# USB2UART.net
KiCad netlist of a schematic drawn in Altium Designer
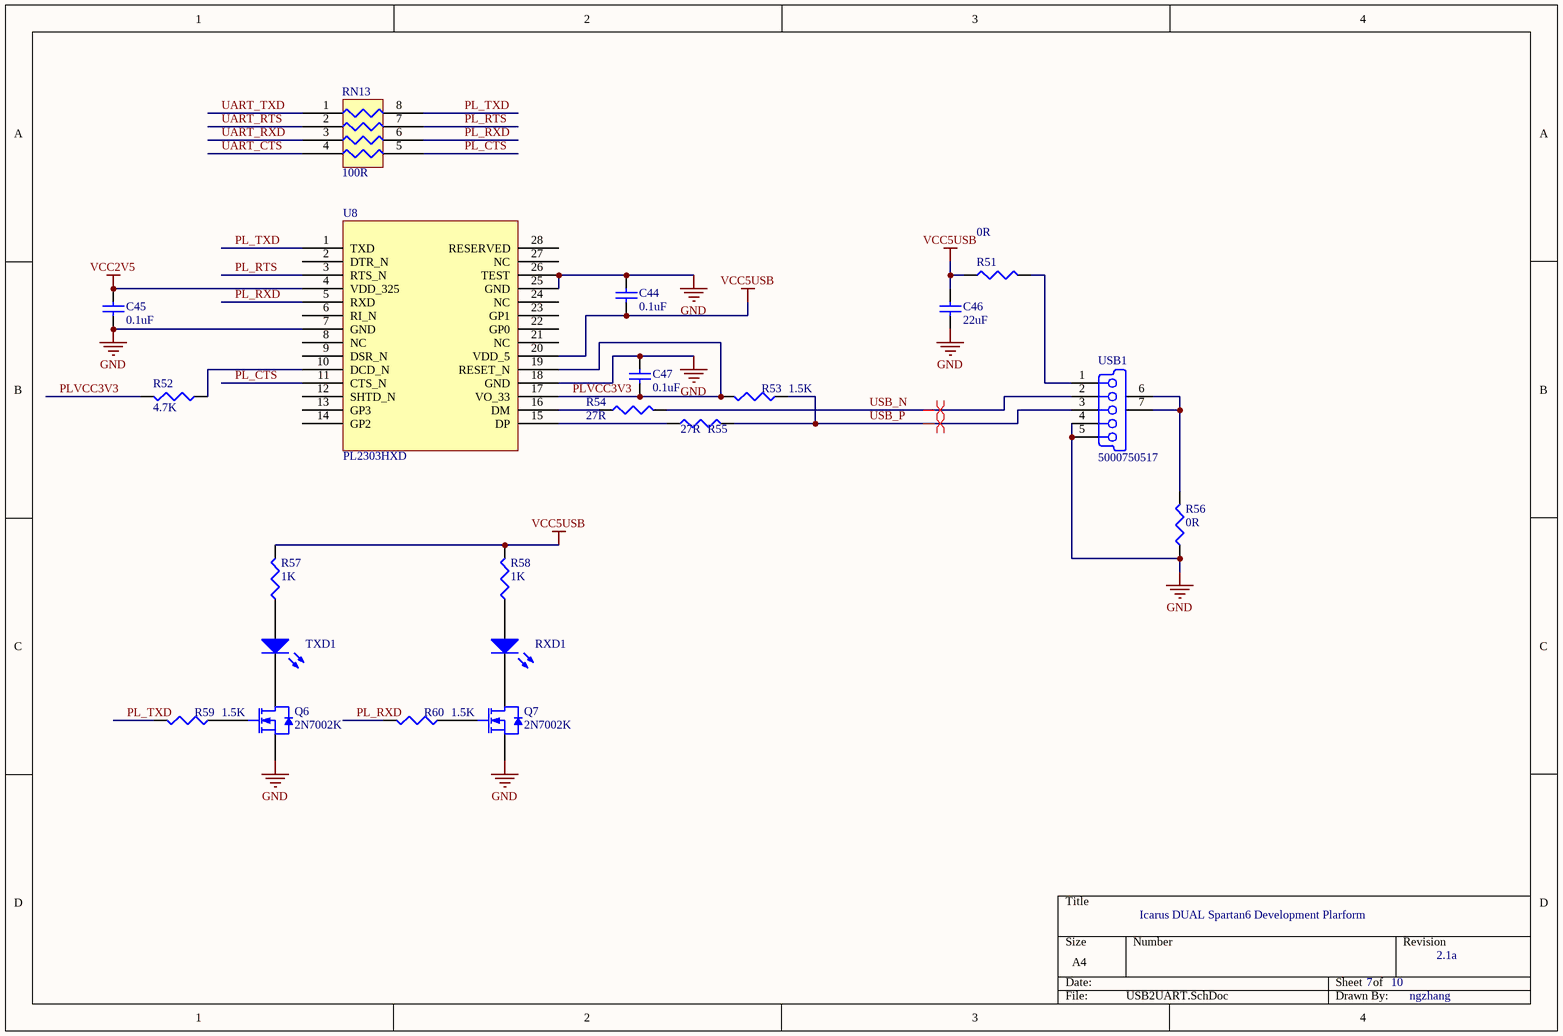
[diagram p0: USB2UART.SchDoc]

(export (version "E")
  (design (tool "Eeschema 10.0.6"))
  (components
    (comp (ref "C44")
      (value "0.1uF")
      (footprint "1608[0603]")
      (description "Capacitor (Semiconductor SIM Model)")
      (fields (field (name "PUBLISHER") "Altium Limited"))
      (libsource (lib "Miscellaneous Devices") (part "Cap Semi"))
    )
    (comp (ref "C45")
      (value "0.1uF")
      (footprint "1608[0603]")
      (description "Capacitor (Semiconductor SIM Model)")
      (fields (field (name "PUBLISHER") "Altium Limited"))
      (libsource (lib "Miscellaneous Devices") (part "Cap Semi"))
    )
    (comp (ref "C46")
      (value "22uF")
      (footprint "C1206")
      (description "Capacitor (Semiconductor SIM Model)")
      (fields (field (name "PUBLISHER") "Altium Limited"))
      (libsource (lib "Miscellaneous Devices") (part "Cap Semi"))
    )
    (comp (ref "C47")
      (value "0.1uF")
      (footprint "1608[0603]")
      (description "Capacitor (Semiconductor SIM Model)")
      (fields (field (name "PUBLISHER") "Altium Limited"))
      (libsource (lib "Miscellaneous Devices") (part "Cap Semi"))
    )
    (comp (ref "Q6")
      (value "2N7002K")
      (footprint "SOT23_N")
      (description "N-channel Enhancement Mode Field-effect Transistor")
      (fields (field (name "PUBLISHER") "Altium Limited"))
      (libsource (lib "Philips Discrete MOSFET - Low Power") (part "2N7002"))
    )
    (comp (ref "Q7")
      (value "2N7002K")
      (footprint "SOT23_N")
      (description "N-channel Enhancement Mode Field-effect Transistor")
      (fields (field (name "PUBLISHER") "Altium Limited"))
      (libsource (lib "Philips Discrete MOSFET - Low Power") (part "2N7002"))
    )
    (comp (ref "R51")
      (value "0R")
      (footprint "J1-0603")
      (description "Resistor")
      (fields (field (name "PUBLISHER") "Altium Limited"))
      (libsource (lib "Miscellaneous Devices") (part "Res3"))
    )
    (comp (ref "R52")
      (value "4.7K")
      (footprint "J1-0603")
      (description "Resistor")
      (fields (field (name "PUBLISHER") "Altium Limited"))
      (libsource (lib "Miscellaneous Devices") (part "Res3"))
    )
    (comp (ref "R53")
      (value "1.5K")
      (footprint "J1-0603")
      (description "Resistor")
      (fields (field (name "PUBLISHER") "Altium Limited"))
      (libsource (lib "Miscellaneous Devices") (part "Res3"))
    )
    (comp (ref "R54")
      (value "27R")
      (footprint "J1-0603")
      (description "Resistor")
      (fields (field (name "PUBLISHER") "Altium Limited"))
      (libsource (lib "Miscellaneous Devices") (part "Res3"))
    )
    (comp (ref "R55")
      (value "27R")
      (footprint "J1-0603")
      (description "Resistor")
      (fields (field (name "PUBLISHER") "Altium Limited"))
      (libsource (lib "Miscellaneous Devices") (part "Res3"))
    )
    (comp (ref "R56")
      (value "0R")
      (footprint "J1-0603")
      (description "Resistor")
      (fields (field (name "PUBLISHER") "Altium Limited"))
      (libsource (lib "Miscellaneous Devices") (part "Res3"))
    )
    (comp (ref "R57")
      (value "1K")
      (footprint "J1-0603")
      (description "Resistor")
      (fields (field (name "PUBLISHER") "Altium Limited"))
      (libsource (lib "Miscellaneous Devices") (part "Res3"))
    )
    (comp (ref "R58")
      (value "1K")
      (footprint "J1-0603")
      (description "Resistor")
      (fields (field (name "PUBLISHER") "Altium Limited"))
      (libsource (lib "Miscellaneous Devices") (part "Res3"))
    )
    (comp (ref "R59")
      (value "1.5K")
      (footprint "J1-0603")
      (description "Resistor")
      (fields (field (name "PUBLISHER") "Altium Limited"))
      (libsource (lib "Miscellaneous Devices") (part "Res3"))
    )
    (comp (ref "R60")
      (value "1.5K")
      (footprint "J1-0603")
      (description "Resistor")
      (fields (field (name "PUBLISHER") "Altium Limited"))
      (libsource (lib "Miscellaneous Devices") (part "Res3"))
    )
    (comp (ref "RN13") (value "100R") (footprint "EXBV8V") (libsource (lib "S6") (part "RES4PACK")))
    (comp (ref "RXD1")
      (value "LED3")
      (footprint "CD1608-0603")
      (description "Typical BLUE SiC LED")
      (fields (field (name "PUBLISHER") "Altium Limited"))
      (libsource (lib "Miscellaneous Devices") (part "LED3"))
    )
    (comp (ref "TXD1")
      (value "LED3")
      (footprint "CD1608-0603")
      (description "Typical BLUE SiC LED")
      (fields (field (name "PUBLISHER") "Altium Limited"))
      (libsource (lib "Miscellaneous Devices") (part "LED3"))
    )
    (comp (ref "U8") (value "PL2303HXD") (footprint "SSOP28_N") (libsource (lib "S6") (part "PL2303")))
    (comp (ref "USB1")
      (value "5000750517")
      (footprint "5000750517")
      (fields (field (name "PUBLISHER") "Altium Limited"))
      (libsource (lib "Molex Serial Bus Mini USB") (part "5000750517"))
    )
  )
  (nets
    (net (code "1") (name "/PLVCC3V3") (class "Default")
      (node (ref "C47") (pin "1") (pinfunction "1_1") (pintype "passive"))
      (node (ref "R52") (pin "2") (pinfunction "2_2") (pintype "passive"))
      (node (ref "R53") (pin "2") (pinfunction "2_2") (pintype "passive"))
      (node (ref "U8") (pin "17") (pinfunction "VO_33_17") (pintype "power_in"))
      (node (ref "U8") (pin "19") (pinfunction "RESET_N_19") (pintype "power_in"))
    )
    (net (code "2") (name "/PL_CTS") (class "Default")
      (node (ref "RN13") (pin "5") (pinfunction "5_5") (pintype "power_in"))
      (node (ref "U8") (pin "11") (pinfunction "CTS_N_11") (pintype "power_in"))
    )
    (net (code "3") (name "/PL_RTS") (class "Default")
      (node (ref "RN13") (pin "7") (pinfunction "7_7") (pintype "power_in"))
      (node (ref "U8") (pin "3") (pinfunction "RTS_N_3") (pintype "power_in"))
    )
    (net (code "4") (name "/PL_RXD") (class "Default")
      (node (ref "R60") (pin "2") (pinfunction "2_2") (pintype "passive"))
      (node (ref "RN13") (pin "6") (pinfunction "6_6") (pintype "power_in"))
      (node (ref "U8") (pin "5") (pinfunction "RXD_5") (pintype "power_in"))
    )
    (net (code "5") (name "/PL_TXD") (class "Default")
      (node (ref "R59") (pin "2") (pinfunction "2_2") (pintype "passive"))
      (node (ref "RN13") (pin "8") (pinfunction "8_8") (pintype "power_in"))
      (node (ref "U8") (pin "1") (pinfunction "TXD_1") (pintype "power_in"))
    )
    (net (code "6") (name "/UART_CTS") (class "Default")
      (node (ref "RN13") (pin "4") (pinfunction "4_4") (pintype "power_in"))
    )
    (net (code "7") (name "/UART_RTS") (class "Default")
      (node (ref "RN13") (pin "2") (pinfunction "2_2") (pintype "power_in"))
    )
    (net (code "8") (name "/UART_RXD") (class "Default")
      (node (ref "RN13") (pin "3") (pinfunction "3_3") (pintype "power_in"))
    )
    (net (code "9") (name "/UART_TXD") (class "Default")
      (node (ref "RN13") (pin "1") (pinfunction "1_1") (pintype "power_in"))
    )
    (net (code "10") (name "/USB_N") (class "Default")
      (node (ref "R54") (pin "2") (pinfunction "2_2") (pintype "passive"))
      (node (ref "USB1") (pin "2") (pinfunction "D-_2") (pintype "passive"))
    )
    (net (code "11") (name "/USB_P") (class "Default")
      (node (ref "R53") (pin "1") (pinfunction "1_1") (pintype "passive"))
      (node (ref "R55") (pin "2") (pinfunction "2_2") (pintype "passive"))
      (node (ref "USB1") (pin "3") (pinfunction "D+_3") (pintype "passive"))
    )
    (net (code "12") (name "GND") (class "Default")
      (node (ref "C44") (pin "2") (pinfunction "2_2") (pintype "passive"))
      (node (ref "C45") (pin "1") (pinfunction "1_1") (pintype "passive"))
      (node (ref "C46") (pin "1") (pinfunction "1_1") (pintype "passive"))
      (node (ref "C47") (pin "2") (pinfunction "2_2") (pintype "passive"))
      (node (ref "Q6") (pin "2") (pinfunction "S_2") (pintype "passive"))
      (node (ref "Q7") (pin "2") (pinfunction "S_2") (pintype "passive"))
      (node (ref "R56") (pin "1") (pinfunction "1_1") (pintype "passive"))
      (node (ref "U8") (pin "18") (pinfunction "GND_18") (pintype "power_in"))
      (node (ref "U8") (pin "25") (pinfunction "GND_25") (pintype "power_in"))
      (node (ref "U8") (pin "26") (pinfunction "TEST_26") (pintype "power_in"))
      (node (ref "U8") (pin "7") (pinfunction "GND_7") (pintype "power_in"))
      (node (ref "USB1") (pin "4") (pinfunction "ID_4") (pintype "passive"))
      (node (ref "USB1") (pin "5") (pinfunction "GND_5") (pintype "passive"))
    )
    (net (code "13") (name "Net-(Q6-D)") (class "Default")
      (node (ref "Q6") (pin "3") (pinfunction "D_3") (pintype "passive"))
      (node (ref "TXD1") (pin "2") (pinfunction "K_2") (pintype "passive"))
    )
    (net (code "14") (name "Net-(Q6-G)") (class "Default")
      (node (ref "Q6") (pin "1") (pinfunction "G_1") (pintype "passive"))
      (node (ref "R59") (pin "1") (pinfunction "1_1") (pintype "passive"))
    )
    (net (code "15") (name "Net-(Q7-D)") (class "Default")
      (node (ref "Q7") (pin "3") (pinfunction "D_3") (pintype "passive"))
      (node (ref "RXD1") (pin "2") (pinfunction "K_2") (pintype "passive"))
    )
    (net (code "16") (name "Net-(Q7-G)") (class "Default")
      (node (ref "Q7") (pin "1") (pinfunction "G_1") (pintype "passive"))
      (node (ref "R60") (pin "1") (pinfunction "1_1") (pintype "passive"))
    )
    (net (code "17") (name "Net-(RXD1-A)") (class "Default")
      (node (ref "R58") (pin "1") (pinfunction "1_1") (pintype "passive"))
      (node (ref "RXD1") (pin "1") (pinfunction "A_1") (pintype "passive"))
    )
    (net (code "18") (name "Net-(TXD1-A)") (class "Default")
      (node (ref "R57") (pin "1") (pinfunction "1_1") (pintype "passive"))
      (node (ref "TXD1") (pin "1") (pinfunction "A_1") (pintype "passive"))
    )
    (net (code "19") (name "Net-(U8-DCD_N)") (class "Default")
      (node (ref "R52") (pin "1") (pinfunction "1_1") (pintype "passive"))
      (node (ref "U8") (pin "10") (pinfunction "DCD_N_10") (pintype "power_in"))
    )
    (net (code "20") (name "Net-(U8-DM)") (class "Default")
      (node (ref "R54") (pin "1") (pinfunction "1_1") (pintype "passive"))
      (node (ref "U8") (pin "16") (pinfunction "DM_16") (pintype "power_in"))
    )
    (net (code "21") (name "Net-(U8-DP)") (class "Default")
      (node (ref "R55") (pin "1") (pinfunction "1_1") (pintype "passive"))
      (node (ref "U8") (pin "15") (pinfunction "DP_15") (pintype "power_in"))
    )
    (net (code "22") (name "Net-(USB1-MH1)") (class "Default")
      (node (ref "R56") (pin "2") (pinfunction "2_2") (pintype "passive"))
      (node (ref "USB1") (pin "6") (pinfunction "MH1_6") (pintype "passive"))
      (node (ref "USB1") (pin "7") (pinfunction "MH2_7") (pintype "passive"))
    )
    (net (code "23") (name "Net-(USB1-V_BUS)") (class "Default")
      (node (ref "R51") (pin "2") (pinfunction "2_2") (pintype "passive"))
      (node (ref "USB1") (pin "1") (pinfunction "V_BUS_1") (pintype "passive"))
    )
    (net (code "24") (name "VCC2V5") (class "Default")
      (node (ref "C45") (pin "2") (pinfunction "2_2") (pintype "passive"))
      (node (ref "U8") (pin "4") (pinfunction "VDD_325_4") (pintype "power_in"))
    )
    (net (code "25") (name "VCC5USB") (class "Default")
      (node (ref "C44") (pin "1") (pinfunction "1_1") (pintype "passive"))
      (node (ref "C46") (pin "2") (pinfunction "2_2") (pintype "passive"))
      (node (ref "R51") (pin "1") (pinfunction "1_1") (pintype "passive"))
      (node (ref "R57") (pin "2") (pinfunction "2_2") (pintype "passive"))
      (node (ref "R58") (pin "2") (pinfunction "2_2") (pintype "passive"))
      (node (ref "U8") (pin "20") (pinfunction "VDD_5_20") (pintype "power_in"))
    )
    (net (code "26") (name "unconnected-(U8-DSR_N-Pad9)") (class "Default")
      (node (ref "U8") (pin "9") (pinfunction "DSR_N_9") (pintype "power_in"))
    )
    (net (code "27") (name "unconnected-(U8-DTR_N-Pad2)") (class "Default")
      (node (ref "U8") (pin "2") (pinfunction "DTR_N_2") (pintype "power_in"))
    )
    (net (code "28") (name "unconnected-(U8-GP0-Pad22)") (class "Default")
      (node (ref "U8") (pin "22") (pinfunction "GP0_22") (pintype "power_in"))
    )
    (net (code "29") (name "unconnected-(U8-GP1-Pad23)") (class "Default")
      (node (ref "U8") (pin "23") (pinfunction "GP1_23") (pintype "power_in"))
    )
    (net (code "30") (name "unconnected-(U8-GP2-Pad14)") (class "Default")
      (node (ref "U8") (pin "14") (pinfunction "GP2_14") (pintype "power_in"))
    )
    (net (code "31") (name "unconnected-(U8-GP3-Pad13)") (class "Default")
      (node (ref "U8") (pin "13") (pinfunction "GP3_13") (pintype "power_in"))
    )
    (net (code "32") (name "unconnected-(U8-NC-Pad8)") (class "Default")
      (node (ref "U8") (pin "8") (pinfunction "NC_8") (pintype "power_in"))
    )
    (net (code "33") (name "unconnected-(U8-NC-Pad21)") (class "Default")
      (node (ref "U8") (pin "21") (pinfunction "NC_21") (pintype "power_in"))
    )
    (net (code "34") (name "unconnected-(U8-NC-Pad24)") (class "Default")
      (node (ref "U8") (pin "24") (pinfunction "NC_24") (pintype "power_in"))
    )
    (net (code "35") (name "unconnected-(U8-NC-Pad27)") (class "Default")
      (node (ref "U8") (pin "27") (pinfunction "NC_27") (pintype "power_in"))
    )
    (net (code "36") (name "unconnected-(U8-RESERVED-Pad28)") (class "Default")
      (node (ref "U8") (pin "28") (pinfunction "RESERVED_28") (pintype "power_in"))
    )
    (net (code "37") (name "unconnected-(U8-RI_N-Pad6)") (class "Default")
      (node (ref "U8") (pin "6") (pinfunction "RI_N_6") (pintype "power_in"))
    )
    (net (code "38") (name "unconnected-(U8-SHTD_N-Pad12)") (class "Default")
      (node (ref "U8") (pin "12") (pinfunction "SHTD_N_12") (pintype "power_in"))
    )
  )
)
